# master-v13.net
KiCad netlist of a schematic drawn in EAGLE
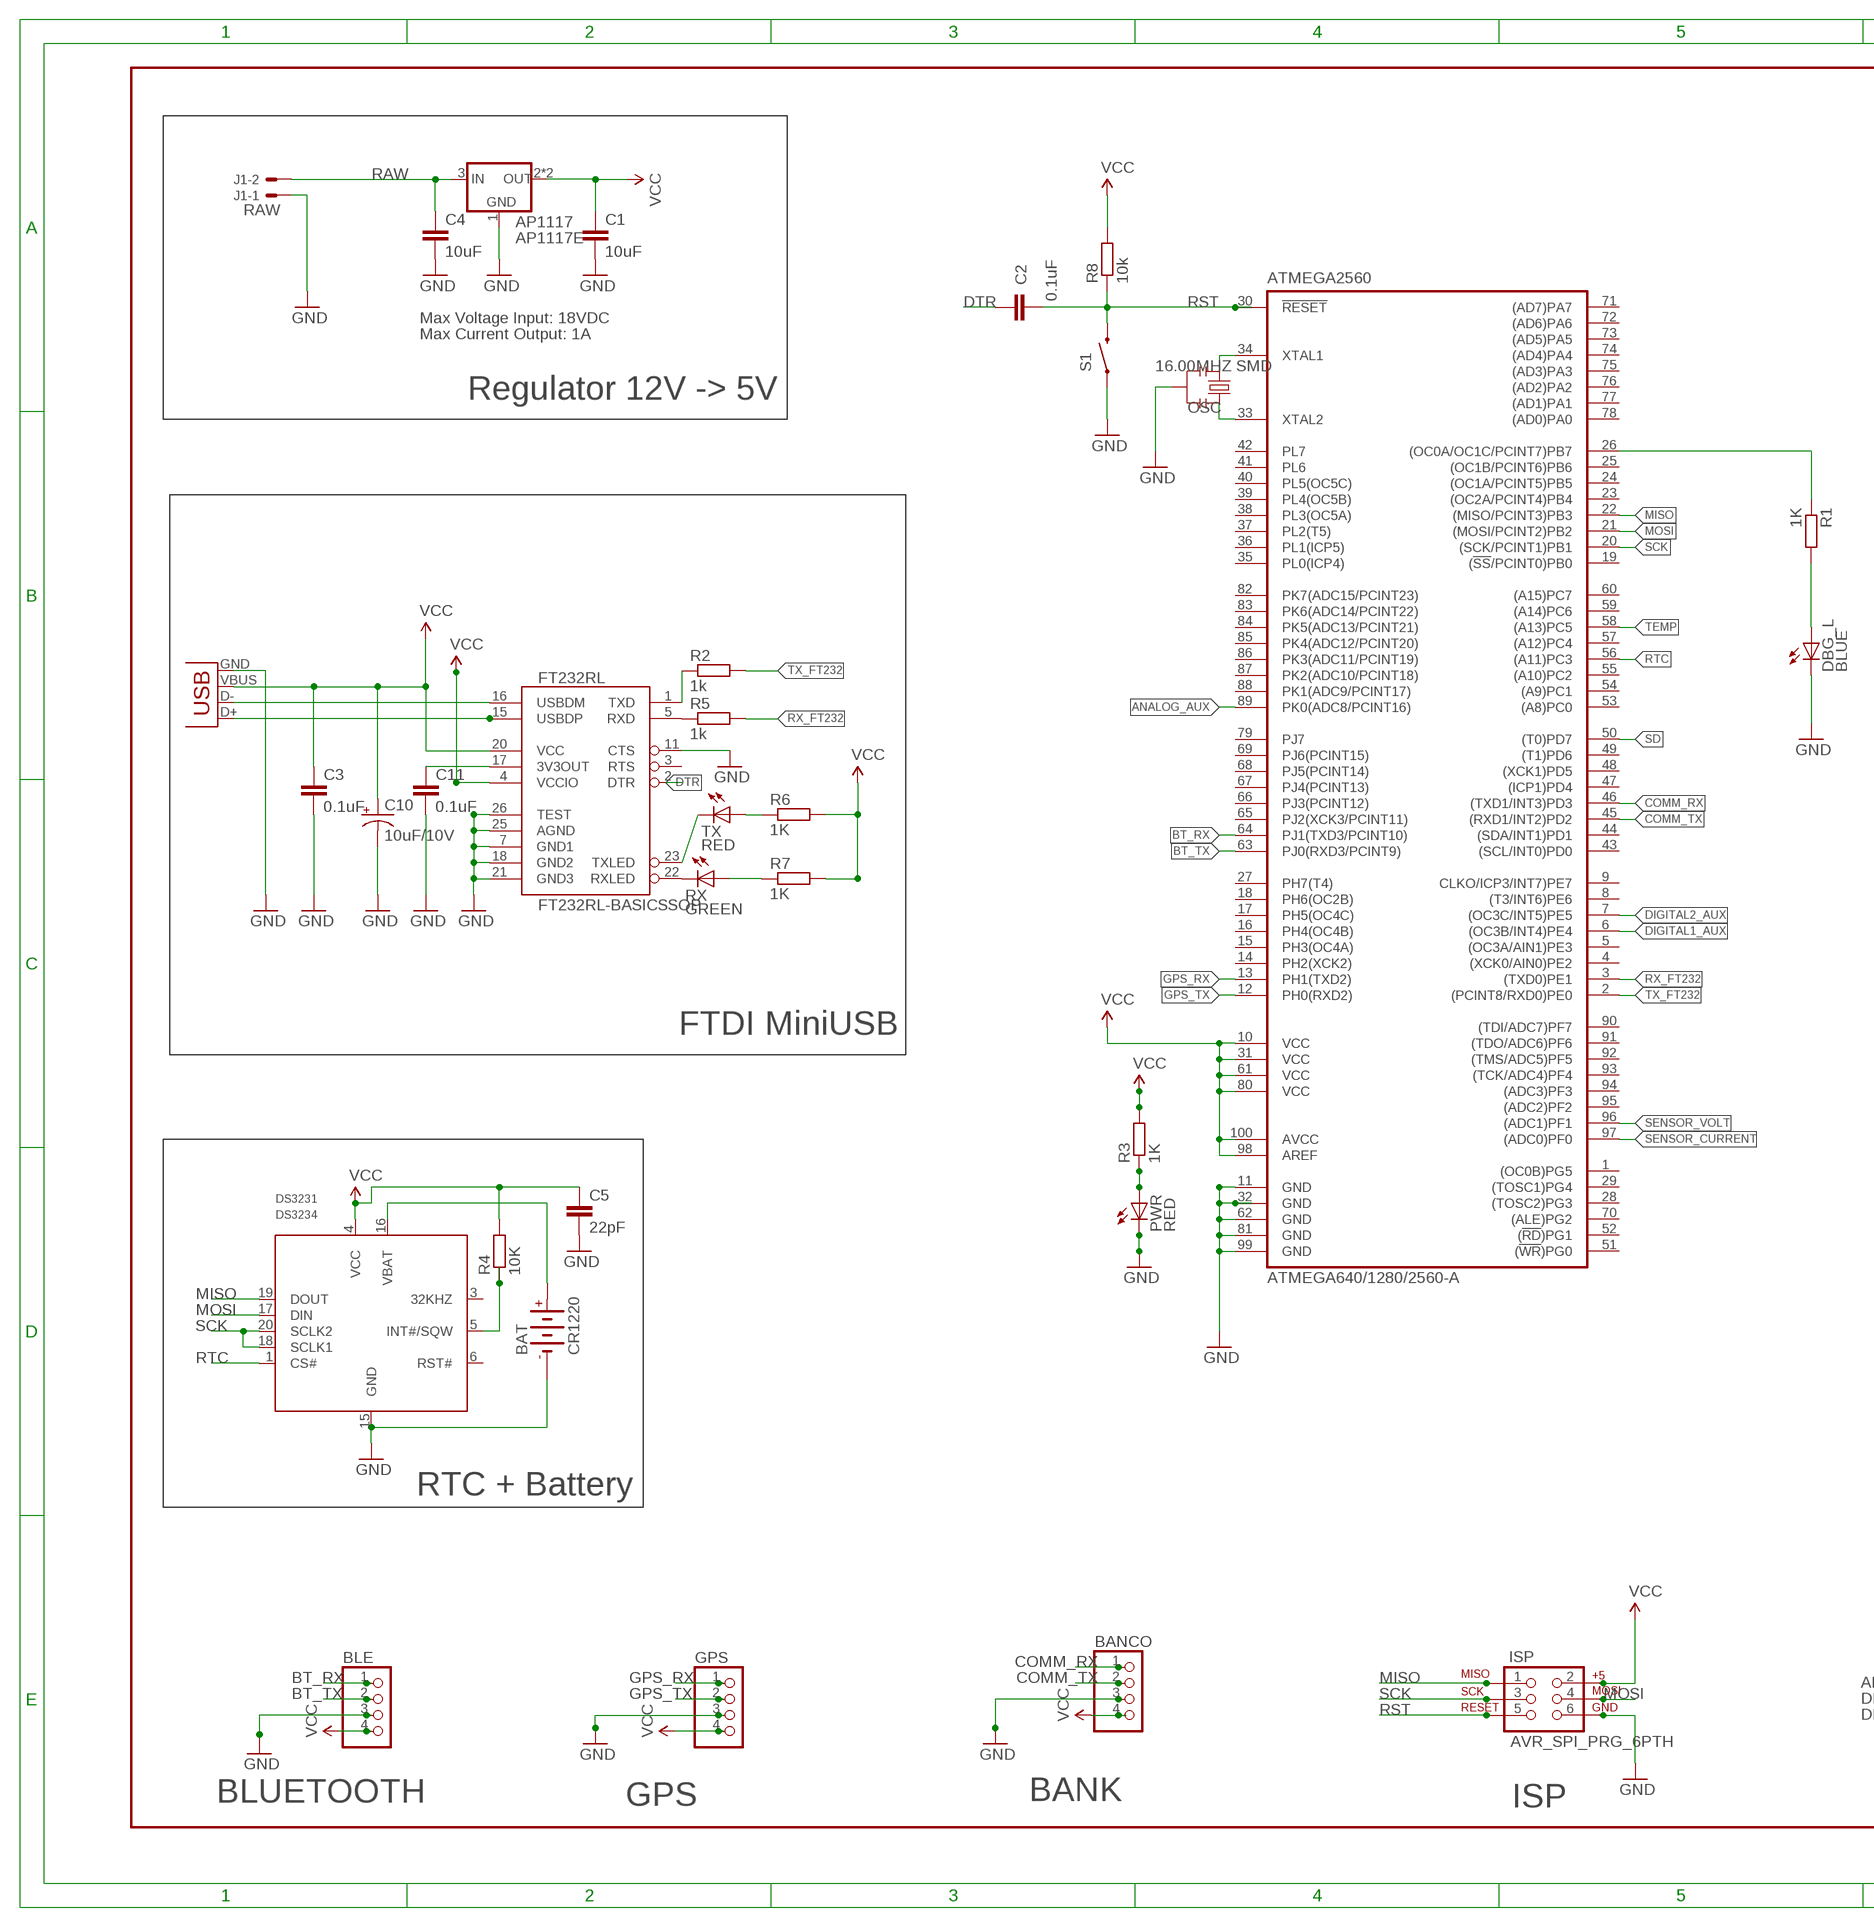
[diagram p0: schematic, sheet 1, part 1 of 2]
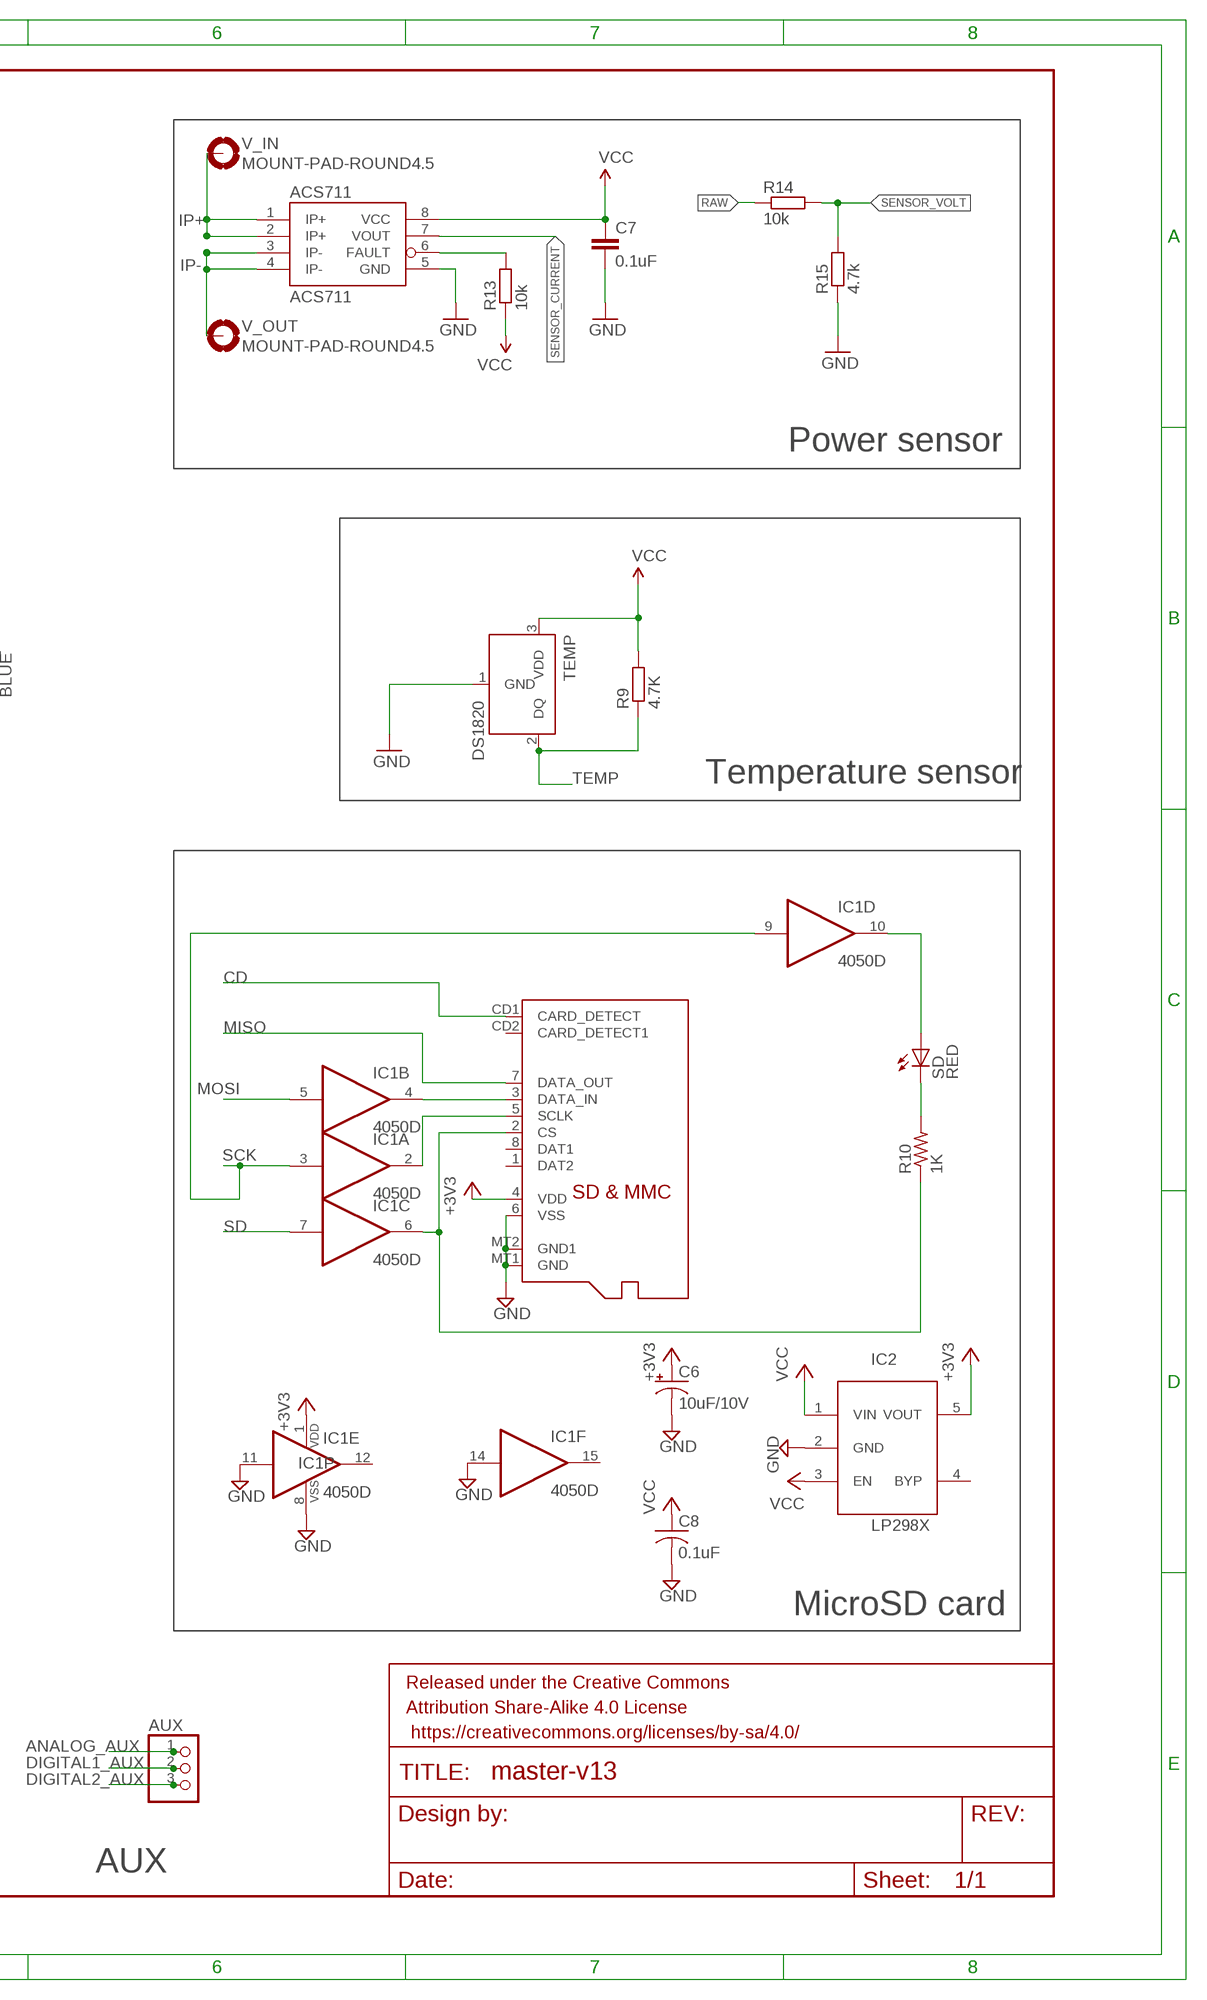
[diagram p1: schematic, sheet 1, part 2 of 2]

(export (version "E")
  (design (tool "Eeschema 10.0.6"))
  (components
    (comp (ref "ACS711")
      (value "ACS711")
      (footprint "eagle-import:SOIC8")
      (fields (field (name "MPN") "ACS711KLCTR-25AB-T"))
      (libsource (lib "eagle-import") (part "ACS711"))
    )
    (comp (ref "AP1117")
      (value "AP1117E")
      (footprint "eagle-import:SOT223")
      (fields (field (name "MPN") "AP1117E50G-13"))
      (libsource (lib "eagle-import") (part "AP1117E"))
    )
    (comp (ref "ATMEGA2560")
      (value "ATMEGA640/1280/2560-A")
      (footprint "eagle-import:TQFP100A")
      (libsource (lib "eagle-import") (part "ATMEGA640/1280/2560-A"))
    )
    (comp (ref "AUX")
      (value "PINHD-1X3")
      (footprint "eagle-import:1X03")
      (libsource (lib "eagle-import") (part "PINHD-1X3"))
    )
    (comp (ref "BANCO")
      (value "PINHD-1X4")
      (footprint "eagle-import:1X04")
      (libsource (lib "eagle-import") (part "PINHD-1X4"))
    )
    (comp (ref "BAT")
      (value "CR1220")
      (footprint "eagle-import:CR1220")
      (fields (field (name "MF") "SANYO, HAWKER, PANASONIC BATTE"))
      (libsource (lib "eagle-import") (part "CR1220"))
    )
    (comp (ref "BLE")
      (value "PINHD-1X4")
      (footprint "eagle-import:1X04")
      (libsource (lib "eagle-import") (part "PINHD-1X4"))
    )
    (comp (ref "C1")
      (value "10uF")
      (footprint "eagle-import:C0805K")
      (fields (field (name "MPN") "0805ZD106KAT2A"))
      (libsource (lib "eagle-import") (part "C-EUC0805K"))
    )
    (comp (ref "C2")
      (value "0.1uF")
      (footprint "eagle-import:C0805K")
      (fields (field (name "MPN") "MC0603B104K500CT"))
      (libsource (lib "eagle-import") (part "C-EUC0805K"))
    )
    (comp (ref "C3")
      (value "0.1uF")
      (footprint "eagle-import:0402-CAP")
      (fields (field (name "MPN") "MC0603B104K500CT"))
      (libsource (lib "eagle-import") (part "CAP0402-CAP"))
    )
    (comp (ref "C4")
      (value "10uF")
      (footprint "eagle-import:C0805K")
      (fields (field (name "MPN") "0805ZD106KAT2A"))
      (libsource (lib "eagle-import") (part "C-EUC0805K"))
    )
    (comp (ref "C5")
      (value "22pF")
      (footprint "eagle-import:0402-CAP")
      (fields (field (name "MPN") "MC0603B104K500CT"))
      (libsource (lib "eagle-import") (part "CAP0402-CAP"))
    )
    (comp (ref "C6")
      (value "10uF/10V")
      (footprint "eagle-import:A_3216-18R")
      (fields (field (name "MPN") "TAJP106M010RNJ"))
      (libsource (lib "eagle-import") (part "CPOL-USA/3216-18R"))
    )
    (comp (ref "C7")
      (value "0.1uF")
      (footprint "eagle-import:C0805K")
      (fields (field (name "MPN") "MC0603B104K500CT"))
      (libsource (lib "eagle-import") (part "C-EUC0805K"))
    )
    (comp (ref "C8")
      (value "0.1uF")
      (footprint "eagle-import:C0805K")
      (fields (field (name "MPN") "MC0603B104K500CT"))
      (libsource (lib "eagle-import") (part "C-USC0805K"))
    )
    (comp (ref "C10")
      (value "10uF/10V")
      (footprint "eagle-import:A_3216-18R")
      (fields (field (name "MPN") "TAJP106M010RNJ"))
      (libsource (lib "eagle-import") (part "CPOL-USA/3216-18R"))
    )
    (comp (ref "C11")
      (value "0.1uF")
      (footprint "eagle-import:0402-CAP")
      (fields (field (name "MPN") "MC0603B104K500CT"))
      (libsource (lib "eagle-import") (part "CAP0402-CAP"))
    )
    (comp (ref "DBG_L")
      (value "BLUE")
      (footprint "eagle-import:CHIPLED_0805")
      (fields (field (name "MPN") "150080BS75000"))
      (libsource (lib "eagle-import") (part "LEDCHIPLED_0805"))
    )
    (comp (ref "DS3231")
      (value "DS3234")
      (footprint "eagle-import:SO-20DW")
      (libsource (lib "eagle-import") (part "DS3234"))
    )
    (comp (ref "FRAME1")
      (value "FRAME-LEDGER")
      (footprint "eagle-import:CREATIVE_COMMONS")
      (fields (field (name "OC_NEWARK") "unknown"))
      (libsource (lib "eagle-import") (part "FRAME-LEDGER"))
    )
    (comp (ref "FT232RL")
      (value "FT232RL-BASICSSOP")
      (footprint "eagle-import:SSOP28DB")
      (libsource (lib "eagle-import") (part "FT232RL-BASICSSOP"))
    )
    (comp (ref "GPS")
      (value "PINHD-1X4")
      (footprint "eagle-import:1X04")
      (libsource (lib "eagle-import") (part "PINHD-1X4"))
    )
    (comp (ref "IC1")
      (value "4050D")
      (footprint "eagle-import:SO16")
      (fields (field (name "MPN") "74HC4050D,653") (field (name "OC_NEWARK") "93X4897"))
      (libsource (lib "eagle-import") (part "4050D"))
    )
    (comp (ref "IC2")
      (value "LP298XS")
      (footprint "eagle-import:SOT23-5L")
      (libsource (lib "eagle-import") (part "LP298XS"))
    )
    (comp (ref "ISP")
      (value "AVR_SPI_PRG_6PTH")
      (footprint "eagle-import:2X3")
      (libsource (lib "eagle-import") (part "AVR_SPI_PRG_6PTH"))
    )
    (comp (ref "J1")
      (value "RAW")
      (footprint "eagle-import:7395-02")
      (libsource (lib "eagle-import") (part "22-?-0205-7028"))
    )
    (comp (ref "OSC")
      (value "16.00MHZ SMD")
      (footprint "eagle-import:RESONATOR-SMD")
      (fields (field (name "MPN") "PBRC8.00HR50X000"))
      (libsource (lib "eagle-import") (part "RESONATOR-SMD"))
    )
    (comp (ref "PWR")
      (value "RED")
      (footprint "eagle-import:CHIPLED_0805")
      (fields (field (name "MPN") "KPT-2012SRC-J4"))
      (libsource (lib "eagle-import") (part "LEDCHIPLED_0805"))
    )
    (comp (ref "R1")
      (value "1K")
      (footprint "eagle-import:R0805")
      (fields (field (name "MF") "VISHAY/DALE") (field (name "MPN") "CRCW08051K00FKTA"))
      (libsource (lib "eagle-import") (part "R-EU_R0805"))
    )
    (comp (ref "R2")
      (value "1k")
      (footprint "eagle-import:R0805")
      (fields (field (name "MF") "VISHAY/DALE") (field (name "MPN") "CRCW08051K00FKTA"))
      (libsource (lib "eagle-import") (part "R-EU_R0805"))
    )
    (comp (ref "R3")
      (value "1K")
      (footprint "eagle-import:R0805")
      (fields (field (name "MF") "VISHAY/DALE") (field (name "MPN") "CRCW08051K00FKTA"))
      (libsource (lib "eagle-import") (part "R-EU_R0805"))
    )
    (comp (ref "R4")
      (value "10K")
      (footprint "eagle-import:R0805")
      (fields (field (name "MF") "VISHAY/DALE") (field (name "MPN") "CRCW08051K00FKTA"))
      (libsource (lib "eagle-import") (part "R-EU_R0805"))
    )
    (comp (ref "R5")
      (value "1k")
      (footprint "eagle-import:R0805")
      (fields (field (name "MF") "VISHAY/DALE") (field (name "MPN") "CRCW08051K00FKTA"))
      (libsource (lib "eagle-import") (part "R-EU_R0805"))
    )
    (comp (ref "R6")
      (value "1K")
      (footprint "eagle-import:R0805")
      (fields (field (name "MF") "VISHAY/DALE") (field (name "MPN") "CRCW08051K00FKTA"))
      (libsource (lib "eagle-import") (part "R-EU_R0805"))
    )
    (comp (ref "R7")
      (value "1K")
      (footprint "eagle-import:R0805")
      (fields (field (name "MF") "VISHAY/DALE") (field (name "MPN") "CRCW08051K00FKTA"))
      (libsource (lib "eagle-import") (part "R-EU_R0805"))
    )
    (comp (ref "R8")
      (value "10k")
      (footprint "eagle-import:R0805")
      (fields (field (name "MF") "VISHAY/DALE") (field (name "MPN") "CRCW080510K0FKTA"))
      (libsource (lib "eagle-import") (part "R-EU_R0805"))
    )
    (comp (ref "R9")
      (value "4.7K")
      (footprint "eagle-import:R0805")
      (fields (field (name "MF") "VISHAY/DALE") (field (name "MPN") "CRCW080510K0FKTA"))
      (libsource (lib "eagle-import") (part "R-EU_R0805"))
    )
    (comp (ref "R10")
      (value "1K")
      (footprint "eagle-import:R0805")
      (fields (field (name "MF") "VISHAY/DALE") (field (name "MPN") "CRCW08051K00FKTA"))
      (libsource (lib "eagle-import") (part "R-US_R0805"))
    )
    (comp (ref "R13")
      (value "10k")
      (footprint "eagle-import:R0805")
      (fields (field (name "MF") "VISHAY/DALE") (field (name "MPN") "CRCW080510K0FKTA"))
      (libsource (lib "eagle-import") (part "R-EU_R0805"))
    )
    (comp (ref "R14")
      (value "10k")
      (footprint "eagle-import:R0805")
      (fields (field (name "MF") "VISHAY/DALE") (field (name "MPN") "CRCW080510K0FKTA"))
      (libsource (lib "eagle-import") (part "R-EU_R0805"))
    )
    (comp (ref "R15")
      (value "4.7k")
      (footprint "eagle-import:R0805")
      (fields (field (name "MF") "VISHAY/DALE") (field (name "MPN") "CRCW08053K30FKTA"))
      (libsource (lib "eagle-import") (part "R-EU_R0805"))
    )
    (comp (ref "RX")
      (value "GREEN")
      (footprint "eagle-import:CHIPLED_0805")
      (fields (field (name "MPN") "150080VS75000"))
      (libsource (lib "eagle-import") (part "LEDCHIPLED_0805"))
    )
    (comp (ref "S1")
      (value "SWITCH-MOMENTARY-2-SMD-1101NE")
      (footprint "eagle-import:TACTILE-SWITCH-1101NE")
      (libsource (lib "eagle-import") (part "SWITCH-MOMENTARY-2-SMD-1101NE"))
    )
    (comp (ref "SD")
      (value "RED")
      (footprint "eagle-import:CHIP-LED0805")
      (libsource (lib "eagle-import") (part "LEDCHIP-LED0805"))
    )
    (comp (ref "TEMP")
      (value "DS1820")
      (footprint "eagle-import:TO-92")
      (fields (field (name "MPN") "MCP9808-E/MS"))
      (libsource (lib "eagle-import") (part "DS1820"))
    )
    (comp (ref "TX")
      (value "RED")
      (footprint "eagle-import:CHIPLED_0805")
      (fields (field (name "MPN") "KPT-2012SRC-J4"))
      (libsource (lib "eagle-import") (part "LEDCHIPLED_0805"))
    )
    (comp (ref "V_IN")
      (value "MOUNT-PAD-ROUND4.5")
      (footprint "eagle-import:4,5-PAD")
      (libsource (lib "eagle-import") (part "MOUNT-PAD-ROUND4.5"))
    )
    (comp (ref "V_OUT")
      (value "MOUNT-PAD-ROUND4.5")
      (footprint "eagle-import:4,5-PAD")
      (libsource (lib "eagle-import") (part "MOUNT-PAD-ROUND4.5"))
    )
    (comp (ref "X1")
      (value "USB-MB-H")
      (footprint "eagle-import:USB-MB-H")
      (libsource (lib "eagle-import") (part "USB-MB-H"))
    )
    (comp (ref "X2")
      (value "MICROSD")
      (footprint "eagle-import:MICROSD")
      (fields (field (name "MPN") "2908-05WB-MG"))
      (libsource (lib "eagle-import") (part "MICROSD"))
    )
  )
  (nets
    (net (code "1") (name "+3V3") (class "Default")
      (node (ref "C6") (pin "+") (pinfunction "+_+") (pintype "passive"))
      (node (ref "IC1") (pin "1") (pinfunction "VDD_1") (pintype "power_in"))
      (node (ref "IC2") (pin "5") (pinfunction "VOUT_5") (pintype "bidirectional"))
      (node (ref "X2") (pin "4") (pinfunction "VDD_4") (pintype "power_in"))
    )
    (net (code "2") (name "/CD") (class "Default")
      (node (ref "X2") (pin "CD1") (pinfunction "CARD_DETECT_CD1") (pintype "passive"))
    )
    (net (code "3") (name "/IP+") (class "Default")
      (node (ref "ACS711") (pin "1") (pinfunction "IP+_1") (pintype "bidirectional"))
      (node (ref "ACS711") (pin "2") (pinfunction "IP+_2") (pintype "bidirectional"))
      (node (ref "V_IN") (pin "B4,5") (pinfunction "MOUNT_B4,5") (pintype "passive"))
    )
    (net (code "4") (name "/IP-") (class "Default")
      (node (ref "ACS711") (pin "3") (pinfunction "IP-_3") (pintype "bidirectional"))
      (node (ref "ACS711") (pin "4") (pinfunction "IP-_4") (pintype "bidirectional"))
      (node (ref "V_OUT") (pin "B4,5") (pinfunction "MOUNT_B4,5") (pintype "passive"))
    )
    (net (code "5") (name "/RST") (class "Default")
      (node (ref "ATMEGA2560") (pin "30") (pinfunction "~{RESET}_30") (pintype "input"))
      (node (ref "C2") (pin "1") (pinfunction "1_1") (pintype "passive"))
      (node (ref "ISP") (pin "5") (pinfunction "5_5") (pintype "passive"))
      (node (ref "R8") (pin "1") (pinfunction "1_1") (pintype "passive"))
      (node (ref "S1") (pin "P$2") (pinfunction "2_P$2") (pintype "passive"))
    )
    (net (code "6") (name "ANALOG_AUX") (class "Default")
      (node (ref "ATMEGA2560") (pin "89") (pinfunction "PK0(ADC8/PCINT16)_89") (pintype "bidirectional"))
      (node (ref "AUX") (pin "1") (pinfunction "1_1") (pintype "passive"))
    )
    (net (code "7") (name "BT_RX") (class "Default")
      (node (ref "ATMEGA2560") (pin "64") (pinfunction "PJ1(TXD3/PCINT10)_64") (pintype "bidirectional"))
      (node (ref "BLE") (pin "1") (pinfunction "1_1") (pintype "passive"))
    )
    (net (code "8") (name "BT_TX") (class "Default")
      (node (ref "ATMEGA2560") (pin "63") (pinfunction "PJ0(RXD3/PCINT9)_63") (pintype "bidirectional"))
      (node (ref "BLE") (pin "2") (pinfunction "2_2") (pintype "passive"))
    )
    (net (code "9") (name "COMM_RX") (class "Default")
      (node (ref "ATMEGA2560") (pin "46") (pinfunction "(TXD1/INT3)PD3_46") (pintype "bidirectional"))
      (node (ref "BANCO") (pin "1") (pinfunction "1_1") (pintype "passive"))
    )
    (net (code "10") (name "COMM_TX") (class "Default")
      (node (ref "ATMEGA2560") (pin "45") (pinfunction "(RXD1/INT2)PD2_45") (pintype "bidirectional"))
      (node (ref "BANCO") (pin "2") (pinfunction "2_2") (pintype "passive"))
    )
    (net (code "11") (name "DIGITAL1_AUX") (class "Default")
      (node (ref "ATMEGA2560") (pin "6") (pinfunction "(OC3B/INT4)PE4_6") (pintype "bidirectional"))
      (node (ref "AUX") (pin "2") (pinfunction "2_2") (pintype "passive"))
    )
    (net (code "12") (name "DIGITAL2_AUX") (class "Default")
      (node (ref "ATMEGA2560") (pin "7") (pinfunction "(OC3C/INT5)PE5_7") (pintype "bidirectional"))
      (node (ref "AUX") (pin "3") (pinfunction "3_3") (pintype "passive"))
    )
    (net (code "13") (name "DTR") (class "Default")
      (node (ref "C2") (pin "2") (pinfunction "2_2") (pintype "passive"))
      (node (ref "FT232RL") (pin "2") (pinfunction "DTR_2") (pintype "bidirectional"))
    )
    (net (code "14") (name "GND") (class "Default")
      (node (ref "ACS711") (pin "5") (pinfunction "GND_5") (pintype "bidirectional"))
      (node (ref "AP1117") (pin "1") (pinfunction "GND_1") (pintype "input"))
      (node (ref "ATMEGA2560") (pin "11") (pinfunction "GND_11") (pintype "power_in"))
      (node (ref "ATMEGA2560") (pin "32") (pinfunction "GND_32") (pintype "power_in"))
      (node (ref "ATMEGA2560") (pin "62") (pinfunction "GND_62") (pintype "power_in"))
      (node (ref "ATMEGA2560") (pin "81") (pinfunction "GND_81") (pintype "power_in"))
      (node (ref "ATMEGA2560") (pin "99") (pinfunction "GND_99") (pintype "power_in"))
      (node (ref "BANCO") (pin "3") (pinfunction "3_3") (pintype "passive"))
      (node (ref "BAT") (pin "-") (pinfunction "-_-") (pintype "passive"))
      (node (ref "BLE") (pin "3") (pinfunction "3_3") (pintype "passive"))
      (node (ref "C1") (pin "2") (pinfunction "2_2") (pintype "passive"))
      (node (ref "C10") (pin "-") (pinfunction "-_-") (pintype "passive"))
      (node (ref "C11") (pin "2") (pinfunction "2_2") (pintype "passive"))
      (node (ref "C3") (pin "2") (pinfunction "2_2") (pintype "passive"))
      (node (ref "C4") (pin "2") (pinfunction "2_2") (pintype "passive"))
      (node (ref "C5") (pin "2") (pinfunction "2_2") (pintype "passive"))
      (node (ref "C6") (pin "-") (pinfunction "-_-") (pintype "passive"))
      (node (ref "C7") (pin "2") (pinfunction "2_2") (pintype "passive"))
      (node (ref "C8") (pin "2") (pinfunction "2_2") (pintype "passive"))
      (node (ref "DBG_L") (pin "C") (pinfunction "C_C") (pintype "passive"))
      (node (ref "DS3231") (pin "15") (pinfunction "GND_15") (pintype "bidirectional"))
      (node (ref "FT232RL") (pin "11") (pinfunction "CTS_11") (pintype "bidirectional"))
      (node (ref "FT232RL") (pin "18") (pinfunction "GND2_18") (pintype "power_in"))
      (node (ref "FT232RL") (pin "21") (pinfunction "GND3_21") (pintype "power_in"))
      (node (ref "FT232RL") (pin "25") (pinfunction "AGND_25") (pintype "power_in"))
      (node (ref "FT232RL") (pin "26") (pinfunction "TEST_26") (pintype "input"))
      (node (ref "FT232RL") (pin "7") (pinfunction "GND1_7") (pintype "power_in"))
      (node (ref "GPS") (pin "3") (pinfunction "3_3") (pintype "passive"))
      (node (ref "IC1") (pin "11") (pinfunction "I_11") (pintype "input"))
      (node (ref "IC1") (pin "14") (pinfunction "I_14") (pintype "input"))
      (node (ref "IC1") (pin "8") (pinfunction "VSS_8") (pintype "power_in"))
      (node (ref "IC2") (pin "2") (pinfunction "GND_2") (pintype "bidirectional"))
      (node (ref "ISP") (pin "6") (pinfunction "6_6") (pintype "passive"))
      (node (ref "J1") (pin "1") (pinfunction "S_1") (pintype "passive"))
      (node (ref "OSC") (pin "2") (pinfunction "2_2") (pintype "passive"))
      (node (ref "PWR") (pin "C") (pinfunction "C_C") (pintype "passive"))
      (node (ref "R15") (pin "1") (pinfunction "1_1") (pintype "passive"))
      (node (ref "S1") (pin "P$1") (pinfunction "1_P$1") (pintype "passive"))
      (node (ref "TEMP") (pin "1") (pinfunction "GND_1") (pintype "power_in"))
      (node (ref "X1") (pin "GND") (pinfunction "GND_GND") (pintype "bidirectional"))
      (node (ref "X2") (pin "6") (pinfunction "VSS_6") (pintype "power_in"))
      (node (ref "X2") (pin "MT1") (pinfunction "GND_MT1") (pintype "power_in"))
      (node (ref "X2") (pin "MT2") (pinfunction "GND1_MT2") (pintype "power_in"))
    )
    (net (code "15") (name "GPS_RX") (class "Default")
      (node (ref "ATMEGA2560") (pin "13") (pinfunction "PH1(TXD2)_13") (pintype "bidirectional"))
      (node (ref "GPS") (pin "1") (pinfunction "1_1") (pintype "passive"))
    )
    (net (code "16") (name "GPS_TX") (class "Default")
      (node (ref "ATMEGA2560") (pin "12") (pinfunction "PH0(RXD2)_12") (pintype "bidirectional"))
      (node (ref "GPS") (pin "2") (pinfunction "2_2") (pintype "passive"))
    )
    (net (code "17") (name "MISO") (class "Default")
      (node (ref "ATMEGA2560") (pin "22") (pinfunction "(MISO/PCINT3)PB3_22") (pintype "bidirectional"))
      (node (ref "DS3231") (pin "19") (pinfunction "DOUT_19") (pintype "bidirectional"))
      (node (ref "ISP") (pin "1") (pinfunction "1_1") (pintype "passive"))
      (node (ref "X2") (pin "7") (pinfunction "DATA_OUT_7") (pintype "output"))
    )
    (net (code "18") (name "MOSI") (class "Default")
      (node (ref "ATMEGA2560") (pin "21") (pinfunction "(MOSI/PCINT2)PB2_21") (pintype "bidirectional"))
      (node (ref "DS3231") (pin "17") (pinfunction "DIN_17") (pintype "bidirectional"))
      (node (ref "IC1") (pin "5") (pinfunction "I_5") (pintype "input"))
      (node (ref "ISP") (pin "4") (pinfunction "4_4") (pintype "passive"))
    )
    (net (code "19") (name "Net-(ACS711-FAULT)") (class "Default")
      (node (ref "ACS711") (pin "6") (pinfunction "FAULT_6") (pintype "bidirectional"))
      (node (ref "R13") (pin "2") (pinfunction "2_2") (pintype "passive"))
    )
    (net (code "20") (name "Net-(ATMEGA2560-(OC0A{slash}OC1C{slash}PCINT7)PB7)") (class "Default")
      (node (ref "ATMEGA2560") (pin "26") (pinfunction "(OC0A/OC1C/PCINT7)PB7_26") (pintype "bidirectional"))
      (node (ref "R1") (pin "1") (pinfunction "1_1") (pintype "passive"))
    )
    (net (code "21") (name "Net-(ATMEGA2560-XTAL1)") (class "Default")
      (node (ref "ATMEGA2560") (pin "34") (pinfunction "XTAL1_34") (pintype "passive"))
      (node (ref "OSC") (pin "1") (pinfunction "1_1") (pintype "passive"))
    )
    (net (code "22") (name "Net-(ATMEGA2560-XTAL2)") (class "Default")
      (node (ref "ATMEGA2560") (pin "33") (pinfunction "XTAL2_33") (pintype "passive"))
      (node (ref "OSC") (pin "3") (pinfunction "3_3") (pintype "passive"))
    )
    (net (code "23") (name "Net-(DBG_L-PadA)") (class "Default")
      (node (ref "DBG_L") (pin "A") (pinfunction "A_A") (pintype "passive"))
      (node (ref "R1") (pin "2") (pinfunction "2_2") (pintype "passive"))
    )
    (net (code "24") (name "Net-(DS3231-INT#{slash}SQW)") (class "Default")
      (node (ref "DS3231") (pin "5") (pinfunction "INT#/SQW_5") (pintype "bidirectional"))
      (node (ref "R4") (pin "1") (pinfunction "1_1") (pintype "passive"))
    )
    (net (code "25") (name "Net-(DS3231-VBAT)") (class "Default")
      (node (ref "BAT") (pin "+") (pinfunction "+_+") (pintype "passive"))
      (node (ref "DS3231") (pin "16") (pinfunction "VBAT_16") (pintype "bidirectional"))
    )
    (net (code "26") (name "Net-(FT232RL-3V3OUT)") (class "Default")
      (node (ref "C11") (pin "1") (pinfunction "1_1") (pintype "passive"))
      (node (ref "FT232RL") (pin "17") (pinfunction "3V3OUT_17") (pintype "output"))
    )
    (net (code "27") (name "Net-(FT232RL-RXD)") (class "Default")
      (node (ref "FT232RL") (pin "5") (pinfunction "RXD_5") (pintype "input"))
      (node (ref "R5") (pin "1") (pinfunction "1_1") (pintype "passive"))
    )
    (net (code "28") (name "Net-(FT232RL-RXLED)") (class "Default")
      (node (ref "FT232RL") (pin "22") (pinfunction "RXLED_22") (pintype "bidirectional"))
      (node (ref "RX") (pin "C") (pinfunction "C_C") (pintype "passive"))
    )
    (net (code "29") (name "Net-(FT232RL-TXD)") (class "Default")
      (node (ref "FT232RL") (pin "1") (pinfunction "TXD_1") (pintype "output"))
      (node (ref "R2") (pin "1") (pinfunction "1_1") (pintype "passive"))
    )
    (net (code "30") (name "Net-(FT232RL-TXLED)") (class "Default")
      (node (ref "FT232RL") (pin "23") (pinfunction "TXLED_23") (pintype "bidirectional"))
      (node (ref "TX") (pin "C") (pinfunction "C_C") (pintype "passive"))
    )
    (net (code "31") (name "Net-(FT232RL-USBDM)") (class "Default")
      (node (ref "FT232RL") (pin "16") (pinfunction "USBDM_16") (pintype "bidirectional"))
      (node (ref "X1") (pin "D-") (pinfunction "D-_D-") (pintype "bidirectional"))
    )
    (net (code "32") (name "Net-(FT232RL-USBDP)") (class "Default")
      (node (ref "FT232RL") (pin "15") (pinfunction "USBDP_15") (pintype "bidirectional"))
      (node (ref "X1") (pin "D+") (pinfunction "D+_D+") (pintype "bidirectional"))
    )
    (net (code "33") (name "Net-(IC1A-O)") (class "Default")
      (node (ref "IC1") (pin "2") (pinfunction "O_2") (pintype "output"))
      (node (ref "X2") (pin "5") (pinfunction "SCLK_5") (pintype "input"))
    )
    (net (code "34") (name "Net-(IC1B-O)") (class "Default")
      (node (ref "IC1") (pin "4") (pinfunction "O_4") (pintype "output"))
      (node (ref "X2") (pin "3") (pinfunction "DATA_IN_3") (pintype "input"))
    )
    (net (code "35") (name "Net-(IC1C-O)") (class "Default")
      (node (ref "IC1") (pin "6") (pinfunction "O_6") (pintype "output"))
      (node (ref "R10") (pin "1") (pinfunction "1_1") (pintype "passive"))
      (node (ref "X2") (pin "2") (pinfunction "CS_2") (pintype "input"))
    )
    (net (code "36") (name "Net-(IC1D-O)") (class "Default")
      (node (ref "IC1") (pin "10") (pinfunction "O_10") (pintype "output"))
      (node (ref "SD") (pin "A") (pinfunction "A_A") (pintype "passive"))
    )
    (net (code "37") (name "Net-(PWR-PadA)") (class "Default")
      (node (ref "PWR") (pin "A") (pinfunction "A_A") (pintype "passive"))
      (node (ref "R3") (pin "1") (pinfunction "1_1") (pintype "passive"))
    )
    (net (code "38") (name "Net-(R6-Pad1)") (class "Default")
      (node (ref "R6") (pin "1") (pinfunction "1_1") (pintype "passive"))
      (node (ref "TX") (pin "A") (pinfunction "A_A") (pintype "passive"))
    )
    (net (code "39") (name "Net-(R7-Pad1)") (class "Default")
      (node (ref "R7") (pin "1") (pinfunction "1_1") (pintype "passive"))
      (node (ref "RX") (pin "A") (pinfunction "A_A") (pintype "passive"))
    )
    (net (code "40") (name "Net-(R10-Pad2)") (class "Default")
      (node (ref "R10") (pin "2") (pinfunction "2_2") (pintype "passive"))
      (node (ref "SD") (pin "C") (pinfunction "C_C") (pintype "passive"))
    )
    (net (code "41") (name "RAW") (class "Default")
      (node (ref "AP1117") (pin "3") (pinfunction "IN_3") (pintype "input"))
      (node (ref "C4") (pin "1") (pinfunction "1_1") (pintype "passive"))
      (node (ref "J1") (pin "2") (pinfunction "S_2") (pintype "passive"))
      (node (ref "R14") (pin "1") (pinfunction "1_1") (pintype "passive"))
    )
    (net (code "42") (name "RTC") (class "Default")
      (node (ref "ATMEGA2560") (pin "56") (pinfunction "(A11)PC3_56") (pintype "bidirectional"))
      (node (ref "DS3231") (pin "1") (pinfunction "CS#_1") (pintype "bidirectional"))
    )
    (net (code "43") (name "RX_FT232") (class "Default")
      (node (ref "ATMEGA2560") (pin "3") (pinfunction "(TXD0)PE1_3") (pintype "bidirectional"))
      (node (ref "R5") (pin "2") (pinfunction "2_2") (pintype "passive"))
    )
    (net (code "44") (name "SCK") (class "Default")
      (node (ref "ATMEGA2560") (pin "20") (pinfunction "(SCK/PCINT1)PB1_20") (pintype "bidirectional"))
      (node (ref "DS3231") (pin "18") (pinfunction "SCLK1_18") (pintype "bidirectional"))
      (node (ref "DS3231") (pin "20") (pinfunction "SCLK2_20") (pintype "bidirectional"))
      (node (ref "IC1") (pin "3") (pinfunction "I_3") (pintype "input"))
      (node (ref "IC1") (pin "9") (pinfunction "I_9") (pintype "input"))
      (node (ref "ISP") (pin "3") (pinfunction "3_3") (pintype "passive"))
    )
    (net (code "45") (name "SD") (class "Default")
      (node (ref "ATMEGA2560") (pin "50") (pinfunction "(T0)PD7_50") (pintype "bidirectional"))
      (node (ref "IC1") (pin "7") (pinfunction "I_7") (pintype "input"))
    )
    (net (code "46") (name "SENSOR_CURRENT") (class "Default")
      (node (ref "ACS711") (pin "7") (pinfunction "VOUT_7") (pintype "bidirectional"))
      (node (ref "ATMEGA2560") (pin "97") (pinfunction "(ADC0)PF0_97") (pintype "bidirectional"))
    )
    (net (code "47") (name "SENSOR_VOLT") (class "Default")
      (node (ref "ATMEGA2560") (pin "96") (pinfunction "(ADC1)PF1_96") (pintype "bidirectional"))
      (node (ref "R14") (pin "2") (pinfunction "2_2") (pintype "passive"))
      (node (ref "R15") (pin "2") (pinfunction "2_2") (pintype "passive"))
    )
    (net (code "48") (name "TEMP") (class "Default")
      (node (ref "ATMEGA2560") (pin "58") (pinfunction "(A13)PC5_58") (pintype "bidirectional"))
      (node (ref "R9") (pin "1") (pinfunction "1_1") (pintype "passive"))
      (node (ref "TEMP") (pin "2") (pinfunction "DQ_2") (pintype "output"))
    )
    (net (code "49") (name "TX_FT232") (class "Default")
      (node (ref "ATMEGA2560") (pin "2") (pinfunction "(PCINT8/RXD0)PE0_2") (pintype "bidirectional"))
      (node (ref "R2") (pin "2") (pinfunction "2_2") (pintype "passive"))
    )
    (net (code "50") (name "VCC") (class "Default")
      (node (ref "ACS711") (pin "8") (pinfunction "VCC_8") (pintype "bidirectional"))
      (node (ref "AP1117") (pin "2") (pinfunction "OUT_2") (pintype "passive"))
      (node (ref "AP1117") (pin "4") (pinfunction "OUT_4") (pintype "passive"))
      (node (ref "ATMEGA2560") (pin "10") (pinfunction "VCC_10") (pintype "power_in"))
      (node (ref "ATMEGA2560") (pin "100") (pinfunction "AVCC_100") (pintype "power_in"))
      (node (ref "ATMEGA2560") (pin "31") (pinfunction "VCC_31") (pintype "power_in"))
      (node (ref "ATMEGA2560") (pin "61") (pinfunction "VCC_61") (pintype "power_in"))
      (node (ref "ATMEGA2560") (pin "80") (pinfunction "VCC_80") (pintype "power_in"))
      (node (ref "ATMEGA2560") (pin "98") (pinfunction "AREF_98") (pintype "passive"))
      (node (ref "BANCO") (pin "4") (pinfunction "4_4") (pintype "passive"))
      (node (ref "BLE") (pin "4") (pinfunction "4_4") (pintype "passive"))
      (node (ref "C1") (pin "1") (pinfunction "1_1") (pintype "passive"))
      (node (ref "C10") (pin "+") (pinfunction "+_+") (pintype "passive"))
      (node (ref "C3") (pin "1") (pinfunction "1_1") (pintype "passive"))
      (node (ref "C5") (pin "1") (pinfunction "1_1") (pintype "passive"))
      (node (ref "C7") (pin "1") (pinfunction "1_1") (pintype "passive"))
      (node (ref "C8") (pin "1") (pinfunction "1_1") (pintype "passive"))
      (node (ref "DS3231") (pin "4") (pinfunction "VCC_4") (pintype "bidirectional"))
      (node (ref "FT232RL") (pin "20") (pinfunction "VCC_20") (pintype "power_in"))
      (node (ref "FT232RL") (pin "4") (pinfunction "VCCIO_4") (pintype "power_in"))
      (node (ref "GPS") (pin "4") (pinfunction "4_4") (pintype "passive"))
      (node (ref "IC2") (pin "1") (pinfunction "VIN_1") (pintype "bidirectional"))
      (node (ref "IC2") (pin "3") (pinfunction "EN_3") (pintype "bidirectional"))
      (node (ref "ISP") (pin "2") (pinfunction "2_2") (pintype "passive"))
      (node (ref "R13") (pin "1") (pinfunction "1_1") (pintype "passive"))
      (node (ref "R3") (pin "2") (pinfunction "2_2") (pintype "passive"))
      (node (ref "R4") (pin "2") (pinfunction "2_2") (pintype "passive"))
      (node (ref "R6") (pin "2") (pinfunction "2_2") (pintype "passive"))
      (node (ref "R7") (pin "2") (pinfunction "2_2") (pintype "passive"))
      (node (ref "R8") (pin "2") (pinfunction "2_2") (pintype "passive"))
      (node (ref "R9") (pin "2") (pinfunction "2_2") (pintype "passive"))
      (node (ref "TEMP") (pin "3") (pinfunction "VDD_3") (pintype "input"))
      (node (ref "X1") (pin "VBUS") (pinfunction "VBUS_VBUS") (pintype "bidirectional"))
    )
    (net (code "51") (name "unconnected-(ATMEGA2560-(A8)PC0-Pad53)") (class "Default")
      (node (ref "ATMEGA2560") (pin "53") (pinfunction "(A8)PC0_53") (pintype "bidirectional"))
    )
    (net (code "52") (name "unconnected-(ATMEGA2560-(A9)PC1-Pad54)") (class "Default")
      (node (ref "ATMEGA2560") (pin "54") (pinfunction "(A9)PC1_54") (pintype "bidirectional"))
    )
    (net (code "53") (name "unconnected-(ATMEGA2560-(A10)PC2-Pad55)") (class "Default")
      (node (ref "ATMEGA2560") (pin "55") (pinfunction "(A10)PC2_55") (pintype "bidirectional"))
    )
    (net (code "54") (name "unconnected-(ATMEGA2560-(A12)PC4-Pad57)") (class "Default")
      (node (ref "ATMEGA2560") (pin "57") (pinfunction "(A12)PC4_57") (pintype "bidirectional"))
    )
    (net (code "55") (name "unconnected-(ATMEGA2560-(A14)PC6-Pad59)") (class "Default")
      (node (ref "ATMEGA2560") (pin "59") (pinfunction "(A14)PC6_59") (pintype "bidirectional"))
    )
    (net (code "56") (name "unconnected-(ATMEGA2560-(A15)PC7-Pad60)") (class "Default")
      (node (ref "ATMEGA2560") (pin "60") (pinfunction "(A15)PC7_60") (pintype "bidirectional"))
    )
    (net (code "57") (name "unconnected-(ATMEGA2560-(AD0)PA0-Pad78)") (class "Default")
      (node (ref "ATMEGA2560") (pin "78") (pinfunction "(AD0)PA0_78") (pintype "bidirectional"))
    )
    (net (code "58") (name "unconnected-(ATMEGA2560-(AD1)PA1-Pad77)") (class "Default")
      (node (ref "ATMEGA2560") (pin "77") (pinfunction "(AD1)PA1_77") (pintype "bidirectional"))
    )
    (net (code "59") (name "unconnected-(ATMEGA2560-(AD2)PA2-Pad76)") (class "Default")
      (node (ref "ATMEGA2560") (pin "76") (pinfunction "(AD2)PA2_76") (pintype "bidirectional"))
    )
    (net (code "60") (name "unconnected-(ATMEGA2560-(AD3)PA3-Pad75)") (class "Default")
      (node (ref "ATMEGA2560") (pin "75") (pinfunction "(AD3)PA3_75") (pintype "bidirectional"))
    )
    (net (code "61") (name "unconnected-(ATMEGA2560-(AD4)PA4-Pad74)") (class "Default")
      (node (ref "ATMEGA2560") (pin "74") (pinfunction "(AD4)PA4_74") (pintype "bidirectional"))
    )
    (net (code "62") (name "unconnected-(ATMEGA2560-(AD5)PA5-Pad73)") (class "Default")
      (node (ref "ATMEGA2560") (pin "73") (pinfunction "(AD5)PA5_73") (pintype "bidirectional"))
    )
    (net (code "63") (name "unconnected-(ATMEGA2560-(AD6)PA6-Pad72)") (class "Default")
      (node (ref "ATMEGA2560") (pin "72") (pinfunction "(AD6)PA6_72") (pintype "bidirectional"))
    )
    (net (code "64") (name "unconnected-(ATMEGA2560-(AD7)PA7-Pad71)") (class "Default")
      (node (ref "ATMEGA2560") (pin "71") (pinfunction "(AD7)PA7_71") (pintype "bidirectional"))
    )
    (net (code "65") (name "unconnected-(ATMEGA2560-(ADC2)PF2-Pad95)") (class "Default")
      (node (ref "ATMEGA2560") (pin "95") (pinfunction "(ADC2)PF2_95") (pintype "bidirectional"))
    )
    (net (code "66") (name "unconnected-(ATMEGA2560-(ADC3)PF3-Pad94)") (class "Default")
      (node (ref "ATMEGA2560") (pin "94") (pinfunction "(ADC3)PF3_94") (pintype "bidirectional"))
    )
    (net (code "67") (name "unconnected-(ATMEGA2560-(ALE)PG2-Pad70)") (class "Default")
      (node (ref "ATMEGA2560") (pin "70") (pinfunction "(ALE)PG2_70") (pintype "bidirectional"))
    )
    (net (code "68") (name "unconnected-(ATMEGA2560-(ICP1)PD4-Pad47)") (class "Default")
      (node (ref "ATMEGA2560") (pin "47") (pinfunction "(ICP1)PD4_47") (pintype "bidirectional"))
    )
    (net (code "69") (name "unconnected-(ATMEGA2560-(OC0B)PG5-Pad1)") (class "Default")
      (node (ref "ATMEGA2560") (pin "1") (pinfunction "(OC0B)PG5_1") (pintype "bidirectional"))
    )
    (net (code "70") (name "unconnected-(ATMEGA2560-(OC1A{slash}PCINT5)PB5-Pad24)") (class "Default")
      (node (ref "ATMEGA2560") (pin "24") (pinfunction "(OC1A/PCINT5)PB5_24") (pintype "bidirectional"))
    )
    (net (code "71") (name "unconnected-(ATMEGA2560-(OC1B{slash}PCINT6)PB6-Pad25)") (class "Default")
      (node (ref "ATMEGA2560") (pin "25") (pinfunction "(OC1B/PCINT6)PB6_25") (pintype "bidirectional"))
    )
    (net (code "72") (name "unconnected-(ATMEGA2560-(OC2A{slash}PCINT4)PB4-Pad23)") (class "Default")
      (node (ref "ATMEGA2560") (pin "23") (pinfunction "(OC2A/PCINT4)PB4_23") (pintype "bidirectional"))
    )
    (net (code "73") (name "unconnected-(ATMEGA2560-(OC3A{slash}AIN1)PE3-Pad5)") (class "Default")
      (node (ref "ATMEGA2560") (pin "5") (pinfunction "(OC3A/AIN1)PE3_5") (pintype "bidirectional"))
    )
    (net (code "74") (name "unconnected-(ATMEGA2560-(SCL{slash}INT0)PD0-Pad43)") (class "Default")
      (node (ref "ATMEGA2560") (pin "43") (pinfunction "(SCL/INT0)PD0_43") (pintype "bidirectional"))
    )
    (net (code "75") (name "unconnected-(ATMEGA2560-(SDA{slash}INT1)PD1-Pad44)") (class "Default")
      (node (ref "ATMEGA2560") (pin "44") (pinfunction "(SDA/INT1)PD1_44") (pintype "bidirectional"))
    )
    (net (code "76") (name "unconnected-(ATMEGA2560-(T1)PD6-Pad49)") (class "Default")
      (node (ref "ATMEGA2560") (pin "49") (pinfunction "(T1)PD6_49") (pintype "bidirectional"))
    )
    (net (code "77") (name "unconnected-(ATMEGA2560-(T3{slash}INT6)PE6-Pad8)") (class "Default")
      (node (ref "ATMEGA2560") (pin "8") (pinfunction "(T3/INT6)PE6_8") (pintype "bidirectional"))
    )
    (net (code "78") (name "unconnected-(ATMEGA2560-(TCK{slash}ADC4)PF4-Pad93)") (class "Default")
      (node (ref "ATMEGA2560") (pin "93") (pinfunction "(TCK/ADC4)PF4_93") (pintype "input"))
    )
    (net (code "79") (name "unconnected-(ATMEGA2560-(TDI{slash}ADC7)PF7-Pad90)") (class "Default")
      (node (ref "ATMEGA2560") (pin "90") (pinfunction "(TDI/ADC7)PF7_90") (pintype "input"))
    )
    (net (code "80") (name "unconnected-(ATMEGA2560-(TDO{slash}ADC6)PF6-Pad91)") (class "Default")
      (node (ref "ATMEGA2560") (pin "91") (pinfunction "(TDO/ADC6)PF6_91") (pintype "output"))
    )
    (net (code "81") (name "unconnected-(ATMEGA2560-(TMS{slash}ADC5)PF5-Pad92)") (class "Default")
      (node (ref "ATMEGA2560") (pin "92") (pinfunction "(TMS/ADC5)PF5_92") (pintype "input"))
    )
    (net (code "82") (name "unconnected-(ATMEGA2560-(TOSC1)PG4-Pad29)") (class "Default")
      (node (ref "ATMEGA2560") (pin "29") (pinfunction "(TOSC1)PG4_29") (pintype "bidirectional"))
    )
    (net (code "83") (name "unconnected-(ATMEGA2560-(TOSC2)PG3-Pad28)") (class "Default")
      (node (ref "ATMEGA2560") (pin "28") (pinfunction "(TOSC2)PG3_28") (pintype "bidirectional"))
    )
    (net (code "84") (name "unconnected-(ATMEGA2560-(XCK0{slash}AIN0)PE2-Pad4)") (class "Default")
      (node (ref "ATMEGA2560") (pin "4") (pinfunction "(XCK0/AIN0)PE2_4") (pintype "bidirectional"))
    )
    (net (code "85") (name "unconnected-(ATMEGA2560-(XCK1)PD5-Pad48)") (class "Default")
      (node (ref "ATMEGA2560") (pin "48") (pinfunction "(XCK1)PD5_48") (pintype "bidirectional"))
    )
    (net (code "86") (name "unconnected-(ATMEGA2560-(~{RD})PG1-Pad52)") (class "Default")
      (node (ref "ATMEGA2560") (pin "52") (pinfunction "(~{RD})PG1_52") (pintype "bidirectional"))
    )
    (net (code "87") (name "unconnected-(ATMEGA2560-(~{SS}{slash}PCINT0)PB0-Pad19)") (class "Default")
      (node (ref "ATMEGA2560") (pin "19") (pinfunction "(~{SS}/PCINT0)PB0_19") (pintype "bidirectional"))
    )
    (net (code "88") (name "unconnected-(ATMEGA2560-(~{WR})PG0-Pad51)") (class "Default")
      (node (ref "ATMEGA2560") (pin "51") (pinfunction "(~{WR})PG0_51") (pintype "bidirectional"))
    )
    (net (code "89") (name "unconnected-(ATMEGA2560-CLKO{slash}ICP3{slash}INT7)PE7-Pad9)") (class "Default")
      (node (ref "ATMEGA2560") (pin "9") (pinfunction "CLKO/ICP3/INT7)PE7_9") (pintype "bidirectional"))
    )
    (net (code "90") (name "unconnected-(ATMEGA2560-PH2(XCK2)-Pad14)") (class "Default")
      (node (ref "ATMEGA2560") (pin "14") (pinfunction "PH2(XCK2)_14") (pintype "bidirectional"))
    )
    (net (code "91") (name "unconnected-(ATMEGA2560-PH3(OC4A)-Pad15)") (class "Default")
      (node (ref "ATMEGA2560") (pin "15") (pinfunction "PH3(OC4A)_15") (pintype "bidirectional"))
    )
    (net (code "92") (name "unconnected-(ATMEGA2560-PH4(OC4B)-Pad16)") (class "Default")
      (node (ref "ATMEGA2560") (pin "16") (pinfunction "PH4(OC4B)_16") (pintype "bidirectional"))
    )
    (net (code "93") (name "unconnected-(ATMEGA2560-PH5(OC4C)-Pad17)") (class "Default")
      (node (ref "ATMEGA2560") (pin "17") (pinfunction "PH5(OC4C)_17") (pintype "bidirectional"))
    )
    (net (code "94") (name "unconnected-(ATMEGA2560-PH6(OC2B)-Pad18)") (class "Default")
      (node (ref "ATMEGA2560") (pin "18") (pinfunction "PH6(OC2B)_18") (pintype "bidirectional"))
    )
    (net (code "95") (name "unconnected-(ATMEGA2560-PH7(T4)-Pad27)") (class "Default")
      (node (ref "ATMEGA2560") (pin "27") (pinfunction "PH7(T4)_27") (pintype "bidirectional"))
    )
    (net (code "96") (name "unconnected-(ATMEGA2560-PJ2(XCK3{slash}PCINT11)-Pad65)") (class "Default")
      (node (ref "ATMEGA2560") (pin "65") (pinfunction "PJ2(XCK3/PCINT11)_65") (pintype "bidirectional"))
    )
    (net (code "97") (name "unconnected-(ATMEGA2560-PJ3(PCINT12)-Pad66)") (class "Default")
      (node (ref "ATMEGA2560") (pin "66") (pinfunction "PJ3(PCINT12)_66") (pintype "bidirectional"))
    )
    (net (code "98") (name "unconnected-(ATMEGA2560-PJ4(PCINT13)-Pad67)") (class "Default")
      (node (ref "ATMEGA2560") (pin "67") (pinfunction "PJ4(PCINT13)_67") (pintype "bidirectional"))
    )
    (net (code "99") (name "unconnected-(ATMEGA2560-PJ5(PCINT14)-Pad68)") (class "Default")
      (node (ref "ATMEGA2560") (pin "68") (pinfunction "PJ5(PCINT14)_68") (pintype "bidirectional"))
    )
    (net (code "100") (name "unconnected-(ATMEGA2560-PJ6(PCINT15)-Pad69)") (class "Default")
      (node (ref "ATMEGA2560") (pin "69") (pinfunction "PJ6(PCINT15)_69") (pintype "bidirectional"))
    )
    (net (code "101") (name "unconnected-(ATMEGA2560-PJ7-Pad79)") (class "Default")
      (node (ref "ATMEGA2560") (pin "79") (pinfunction "PJ7_79") (pintype "bidirectional"))
    )
    (net (code "102") (name "unconnected-(ATMEGA2560-PK1(ADC9{slash}PCINT17)-Pad88)") (class "Default")
      (node (ref "ATMEGA2560") (pin "88") (pinfunction "PK1(ADC9/PCINT17)_88") (pintype "bidirectional"))
    )
    (net (code "103") (name "unconnected-(ATMEGA2560-PK2(ADC10{slash}PCINT18)-Pad87)") (class "Default")
      (node (ref "ATMEGA2560") (pin "87") (pinfunction "PK2(ADC10/PCINT18)_87") (pintype "bidirectional"))
    )
    (net (code "104") (name "unconnected-(ATMEGA2560-PK3(ADC11{slash}PCINT19)-Pad86)") (class "Default")
      (node (ref "ATMEGA2560") (pin "86") (pinfunction "PK3(ADC11/PCINT19)_86") (pintype "bidirectional"))
    )
    (net (code "105") (name "unconnected-(ATMEGA2560-PK4(ADC12{slash}PCINT20)-Pad85)") (class "Default")
      (node (ref "ATMEGA2560") (pin "85") (pinfunction "PK4(ADC12/PCINT20)_85") (pintype "bidirectional"))
    )
    (net (code "106") (name "unconnected-(ATMEGA2560-PK5(ADC13{slash}PCINT21)-Pad84)") (class "Default")
      (node (ref "ATMEGA2560") (pin "84") (pinfunction "PK5(ADC13/PCINT21)_84") (pintype "bidirectional"))
    )
    (net (code "107") (name "unconnected-(ATMEGA2560-PK6(ADC14{slash}PCINT22)-Pad83)") (class "Default")
      (node (ref "ATMEGA2560") (pin "83") (pinfunction "PK6(ADC14/PCINT22)_83") (pintype "bidirectional"))
    )
    (net (code "108") (name "unconnected-(ATMEGA2560-PK7(ADC15{slash}PCINT23)-Pad82)") (class "Default")
      (node (ref "ATMEGA2560") (pin "82") (pinfunction "PK7(ADC15/PCINT23)_82") (pintype "bidirectional"))
    )
    (net (code "109") (name "unconnected-(ATMEGA2560-PL0(ICP4)-Pad35)") (class "Default")
      (node (ref "ATMEGA2560") (pin "35") (pinfunction "PL0(ICP4)_35") (pintype "bidirectional"))
    )
    (net (code "110") (name "unconnected-(ATMEGA2560-PL1(ICP5)-Pad36)") (class "Default")
      (node (ref "ATMEGA2560") (pin "36") (pinfunction "PL1(ICP5)_36") (pintype "bidirectional"))
    )
    (net (code "111") (name "unconnected-(ATMEGA2560-PL2(T5)-Pad37)") (class "Default")
      (node (ref "ATMEGA2560") (pin "37") (pinfunction "PL2(T5)_37") (pintype "bidirectional"))
    )
    (net (code "112") (name "unconnected-(ATMEGA2560-PL3(OC5A)-Pad38)") (class "Default")
      (node (ref "ATMEGA2560") (pin "38") (pinfunction "PL3(OC5A)_38") (pintype "bidirectional"))
    )
    (net (code "113") (name "unconnected-(ATMEGA2560-PL4(OC5B)-Pad39)") (class "Default")
      (node (ref "ATMEGA2560") (pin "39") (pinfunction "PL4(OC5B)_39") (pintype "bidirectional"))
    )
    (net (code "114") (name "unconnected-(ATMEGA2560-PL5(OC5C)-Pad40)") (class "Default")
      (node (ref "ATMEGA2560") (pin "40") (pinfunction "PL5(OC5C)_40") (pintype "bidirectional"))
    )
    (net (code "115") (name "unconnected-(ATMEGA2560-PL6-Pad41)") (class "Default")
      (node (ref "ATMEGA2560") (pin "41") (pinfunction "PL6_41") (pintype "bidirectional"))
    )
    (net (code "116") (name "unconnected-(ATMEGA2560-PL7-Pad42)") (class "Default")
      (node (ref "ATMEGA2560") (pin "42") (pinfunction "PL7_42") (pintype "bidirectional"))
    )
    (net (code "117") (name "unconnected-(DS3231-32KHZ-Pad3)") (class "Default")
      (node (ref "DS3231") (pin "3") (pinfunction "32KHZ_3") (pintype "bidirectional"))
    )
    (net (code "118") (name "unconnected-(DS3231-RST#-Pad6)") (class "Default")
      (node (ref "DS3231") (pin "6") (pinfunction "RST#_6") (pintype "bidirectional"))
    )
    (net (code "119") (name "unconnected-(FT232RL-RTS-Pad3)") (class "Default")
      (node (ref "FT232RL") (pin "3") (pinfunction "RTS_3") (pintype "bidirectional"))
    )
    (net (code "120") (name "unconnected-(IC1E-O-Pad12)") (class "Default")
      (node (ref "IC1") (pin "12") (pinfunction "O_12") (pintype "output"))
    )
    (net (code "121") (name "unconnected-(IC1F-O-Pad15)") (class "Default")
      (node (ref "IC1") (pin "15") (pinfunction "O_15") (pintype "output"))
    )
    (net (code "122") (name "unconnected-(IC2-BYP-Pad4)") (class "Default")
      (node (ref "IC2") (pin "4") (pinfunction "BYP_4") (pintype "bidirectional"))
    )
    (net (code "123") (name "unconnected-(X2-CARD_DETECT1-PadCD2)") (class "Default")
      (node (ref "X2") (pin "CD2") (pinfunction "CARD_DETECT1_CD2") (pintype "passive"))
    )
    (net (code "124") (name "unconnected-(X2-DAT1-Pad8)") (class "Default")
      (node (ref "X2") (pin "8") (pinfunction "DAT1_8") (pintype "bidirectional"))
    )
    (net (code "125") (name "unconnected-(X2-DAT2-Pad1)") (class "Default")
      (node (ref "X2") (pin "1") (pinfunction "DAT2_1") (pintype "bidirectional"))
    )
  )
)
